# SIDE-PROXIMITY-IR-SENSOR.net
KiCad netlist of a schematic drawn in Altium Designer
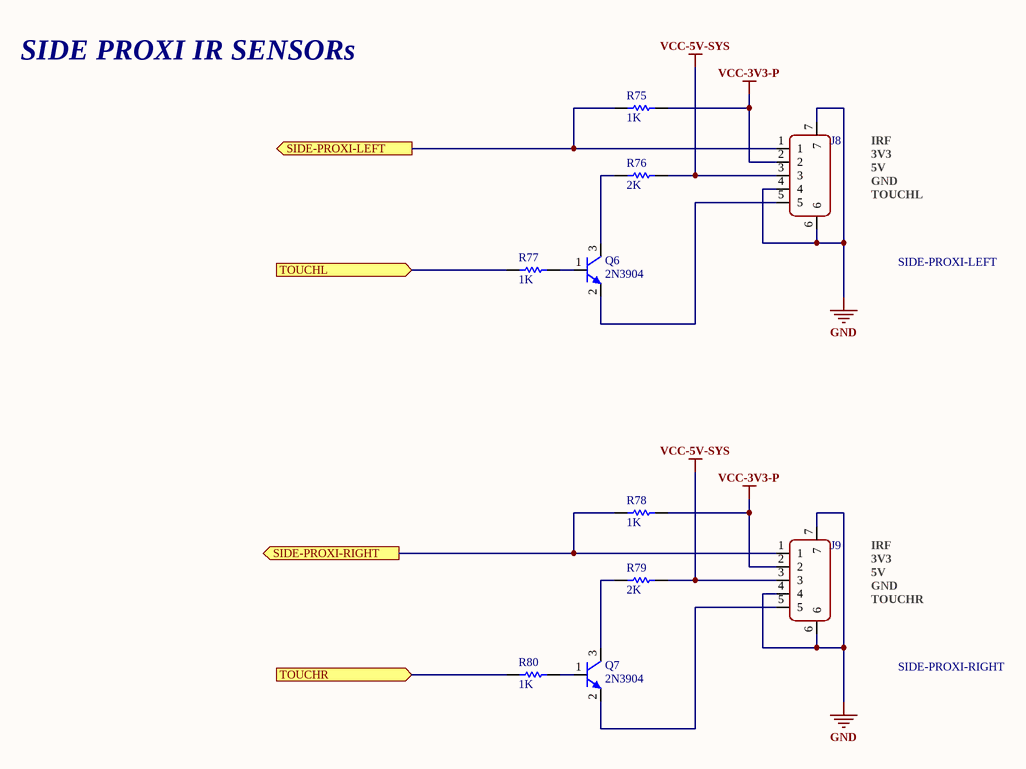
[diagram p0: SIDE-PROXIMITY-IR-SENSOR .SchDoc]

(export (version "E")
  (design (tool "Eeschema 10.0.6"))
  (components
    (comp (ref "J8")
      (value "SIDE-PROXI-LEFT")
      (footprint "CONN-SMD_5P-P1.50_ZX-ZH1.5-5PWT")
      (description "ZX-ZH1.5-5PWT")
      (libsource (lib "DesignLibrary") (part "HDRx5"))
    )
    (comp (ref "J9")
      (value "SIDE-PROXI-RIGHT")
      (footprint "CONN-SMD_5P-P1.50_ZX-ZH1.5-5PWT")
      (description "ZX-ZH1.5-5PWT")
      (libsource (lib "DesignLibrary") (part "HDRx5"))
    )
    (comp (ref "Q6")
      (value "2N3904")
      (footprint "SOT23-3D")
      (libsource (lib "DesignLibrary") (part "NPN-SOT23"))
    )
    (comp (ref "Q7")
      (value "2N3904")
      (footprint "SOT23-3D")
      (libsource (lib "DesignLibrary") (part "NPN-SOT23"))
    )
    (comp (ref "R75")
      (value "1K")
      (footprint "RES-0402")
      (libsource (lib "DesignLibrary") (part "Resistor-1"))
    )
    (comp (ref "R76")
      (value "2K")
      (footprint "RES-0402")
      (libsource (lib "DesignLibrary") (part "Resistor-1"))
    )
    (comp (ref "R77")
      (value "1K")
      (footprint "RES-0402")
      (libsource (lib "DesignLibrary") (part "Resistor-1"))
    )
    (comp (ref "R78")
      (value "1K")
      (footprint "RES-0402")
      (libsource (lib "DesignLibrary") (part "Resistor-1"))
    )
    (comp (ref "R79")
      (value "2K")
      (footprint "RES-0402")
      (libsource (lib "DesignLibrary") (part "Resistor-1"))
    )
    (comp (ref "R80")
      (value "1K")
      (footprint "RES-0402")
      (libsource (lib "DesignLibrary") (part "Resistor-1"))
    )
  )
  (nets
    (net (code "1") (name "/SIDE-PROXI-LEFT") (class "Default")
      (node (ref "J8") (pin "1") (pinfunction "1_1") (pintype "passive"))
      (node (ref "R75") (pin "1") (pintype "passive"))
    )
    (net (code "2") (name "/SIDE-PROXI-RIGHT") (class "Default")
      (node (ref "J9") (pin "1") (pinfunction "1_1") (pintype "passive"))
      (node (ref "R78") (pin "1") (pintype "passive"))
    )
    (net (code "3") (name "/TOUCHL") (class "Default") (node (ref "R77") (pin "1") (pintype "passive")))
    (net (code "4") (name "/TOUCHR") (class "Default") (node (ref "R80") (pin "1") (pintype "passive")))
    (net (code "5") (name "GND") (class "Default")
      (node (ref "J8") (pin "4") (pinfunction "4_4") (pintype "passive"))
      (node (ref "J8") (pin "6") (pinfunction "6_6") (pintype "passive"))
      (node (ref "J8") (pin "7") (pinfunction "7_7") (pintype "passive"))
      (node (ref "J9") (pin "4") (pinfunction "4_4") (pintype "passive"))
      (node (ref "J9") (pin "6") (pinfunction "6_6") (pintype "passive"))
      (node (ref "J9") (pin "7") (pinfunction "7_7") (pintype "passive"))
    )
    (net (code "6") (name "Net-(Q6-B)") (class "Default")
      (node (ref "Q6") (pin "1") (pinfunction "B_1") (pintype "passive"))
      (node (ref "R77") (pin "2") (pintype "passive"))
    )
    (net (code "7") (name "Net-(Q6-C)") (class "Default")
      (node (ref "Q6") (pin "3") (pinfunction "C_3") (pintype "passive"))
      (node (ref "R76") (pin "2") (pintype "passive"))
    )
    (net (code "8") (name "Net-(Q6-E)") (class "Default")
      (node (ref "J8") (pin "5") (pinfunction "5_5") (pintype "passive"))
      (node (ref "Q6") (pin "2") (pinfunction "E_2") (pintype "passive"))
    )
    (net (code "9") (name "Net-(Q7-B)") (class "Default")
      (node (ref "Q7") (pin "1") (pinfunction "B_1") (pintype "passive"))
      (node (ref "R80") (pin "2") (pintype "passive"))
    )
    (net (code "10") (name "Net-(Q7-C)") (class "Default")
      (node (ref "Q7") (pin "3") (pinfunction "C_3") (pintype "passive"))
      (node (ref "R79") (pin "2") (pintype "passive"))
    )
    (net (code "11") (name "Net-(Q7-E)") (class "Default")
      (node (ref "J9") (pin "5") (pinfunction "5_5") (pintype "passive"))
      (node (ref "Q7") (pin "2") (pinfunction "E_2") (pintype "passive"))
    )
    (net (code "12") (name "VCC-3V3-P") (class "Default")
      (node (ref "J8") (pin "2") (pinfunction "2_2") (pintype "passive"))
      (node (ref "J9") (pin "2") (pinfunction "2_2") (pintype "passive"))
      (node (ref "R75") (pin "2") (pintype "passive"))
      (node (ref "R78") (pin "2") (pintype "passive"))
    )
    (net (code "13") (name "VCC-5V-SYS") (class "Default")
      (node (ref "J8") (pin "3") (pinfunction "3_3") (pintype "passive"))
      (node (ref "J9") (pin "3") (pinfunction "3_3") (pintype "passive"))
      (node (ref "R76") (pin "1") (pintype "passive"))
      (node (ref "R79") (pin "1") (pintype "passive"))
    )
  )
)
